# MK8266-O1WF-REV1A.net
KiCad netlist of a schematic drawn in EAGLE
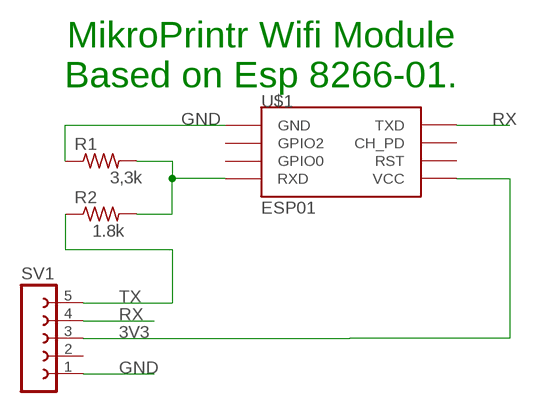
[diagram p0: schematic, sheet 1]

(export (version "E")
  (design (tool "Eeschema 10.0.6"))
  (components
    (comp (ref "R1")
      (value "3,3k")
      (footprint "eagle-import:0204_7")
      (libsource (lib "eagle-import") (part "R-US_0204/7"))
    )
    (comp (ref "R2")
      (value "1.8k")
      (footprint "eagle-import:0204_7")
      (libsource (lib "eagle-import") (part "R-US_0204/7"))
    )
    (comp (ref "SV1")
      (value "FE05-1")
      (footprint "eagle-import:FE05-1")
      (libsource (lib "eagle-import") (part "FE05-1"))
    )
    (comp (ref "U$1")
      (value "ESP01")
      (footprint "eagle-import:ESP01")
      (libsource (lib "eagle-import") (part "ESP01"))
    )
  )
  (nets
    (net (code "1") (name "/3V3") (class "Default")
      (node (ref "SV1") (pin "3") (pinfunction "3_3") (pintype "passive"))
      (node (ref "U$1") (pin "VCC") (pinfunction "VCC_VCC") (pintype "bidirectional"))
    )
    (net (code "2") (name "/GND") (class "Default")
      (node (ref "R1") (pin "1") (pinfunction "1_1") (pintype "passive"))
      (node (ref "SV1") (pin "1") (pinfunction "1_1") (pintype "passive"))
      (node (ref "U$1") (pin "GND") (pinfunction "GND_GND") (pintype "bidirectional"))
    )
    (net (code "3") (name "/RX") (class "Default")
      (node (ref "SV1") (pin "4") (pinfunction "4_4") (pintype "passive"))
      (node (ref "U$1") (pin "TX") (pinfunction "TXD_TX") (pintype "bidirectional"))
    )
    (net (code "4") (name "/TX") (class "Default")
      (node (ref "R2") (pin "1") (pinfunction "1_1") (pintype "passive"))
      (node (ref "SV1") (pin "5") (pinfunction "5_5") (pintype "passive"))
    )
    (net (code "5") (name "Net-(U$1-RXD)") (class "Default")
      (node (ref "R1") (pin "2") (pinfunction "2_2") (pintype "passive"))
      (node (ref "R2") (pin "2") (pinfunction "2_2") (pintype "passive"))
      (node (ref "U$1") (pin "RX") (pinfunction "RXD_RX") (pintype "bidirectional"))
    )
    (net (code "6") (name "unconnected-(SV1-Pad2)") (class "Default")
      (node (ref "SV1") (pin "2") (pinfunction "2_2") (pintype "passive"))
    )
    (net (code "7") (name "unconnected-(U$1-PadCH_PD)") (class "Default")
      (node (ref "U$1") (pin "CH_PD") (pinfunction "CH_PD_CH_PD") (pintype "bidirectional"))
    )
    (net (code "8") (name "unconnected-(U$1-PadGPIO0)") (class "Default")
      (node (ref "U$1") (pin "GPIO0") (pinfunction "GPIO0_GPIO0") (pintype "bidirectional"))
    )
    (net (code "9") (name "unconnected-(U$1-PadGPIO2)") (class "Default")
      (node (ref "U$1") (pin "GPIO2") (pinfunction "GPIO2_GPIO2") (pintype "bidirectional"))
    )
    (net (code "10") (name "unconnected-(U$1-PadRST)") (class "Default")
      (node (ref "U$1") (pin "RST") (pinfunction "RST_RST") (pintype "bidirectional"))
    )
  )
)
